# 3_control.net
KiCad netlist of a schematic drawn in Altium Designer
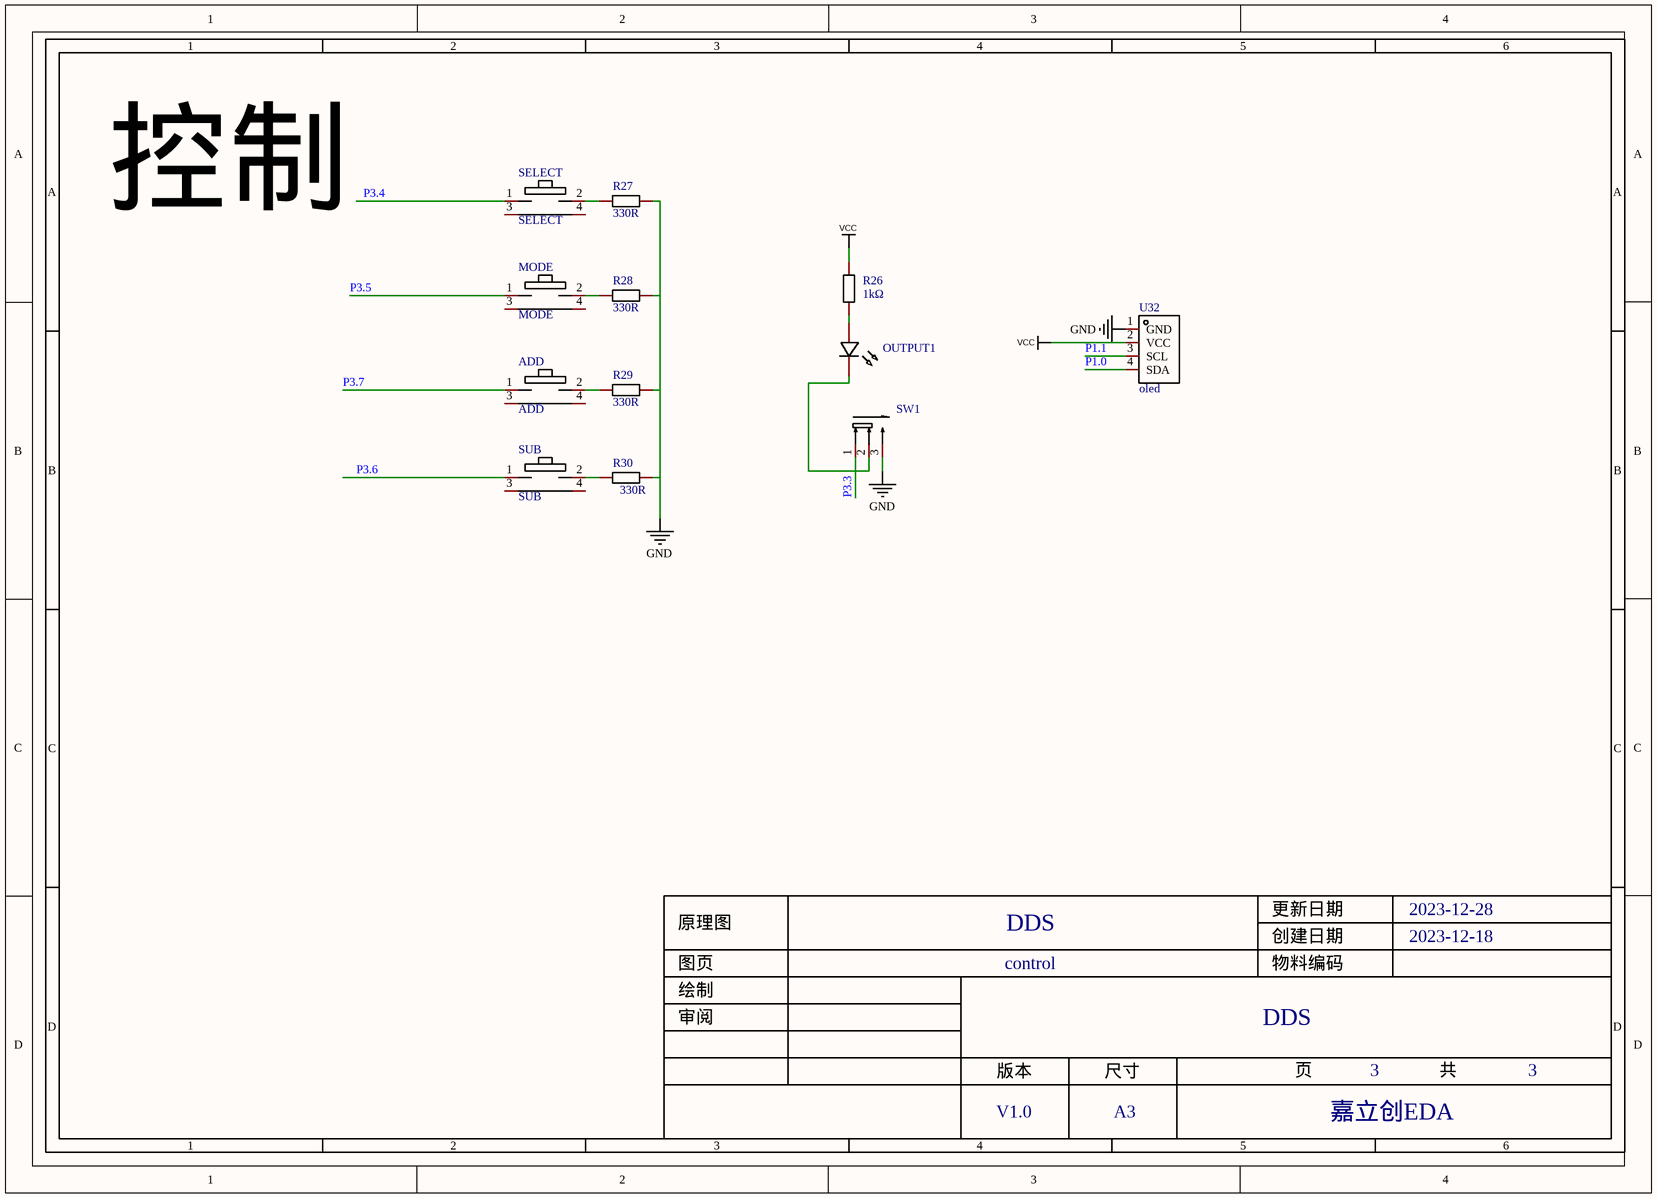
[diagram p0: 3_control.schdoc]

(export (version "E")
  (design (tool "Eeschema 10.0.6"))
  (components
    (comp (ref "ADD")
      (value "ADD")
      (description "电路结构:单刀单掷;按钮作用方向:侧面触动;致动器样式:矩形按钮;照明颜色:-;作用力:180gf ±30gf;开关高度:3.5mm;")
      (fields (field (name "NAME") "ADD") (field (name "MANUFACTURER") "Yuandi(元迪)"))
      (libsource (lib "altium-import") (part "root_0_TS-1087B-B2D2_"))
    )
    (comp (ref "MODE")
      (value "MODE")
      (description "电路结构:单刀单掷;按钮作用方向:侧面触动;致动器样式:矩形按钮;照明颜色:-;作用力:180gf ±30gf;开关高度:3.5mm;")
      (fields (field (name "NAME") "MODE") (field (name "MANUFACTURER") "Yuandi(元迪)"))
      (libsource (lib "altium-import") (part "root_0_TS-1087B-B2D2_"))
    )
    (comp (ref "OUTPUT1") (value "LED_B") (libsource (lib "altium-import") (part "root_3_LED_B_")))
    (comp (ref "R26")
      (value "1kΩ")
      (description "阻值:1kΩ;精度:±1%;功率:125mW;温度系数:±100ppm/℃;电阻类型:厚膜电阻;")
      (fields
        (field (name "NAME") "1kΩ")
        (field (name "MANUFACTURER") "UNI-ROYAL(厚声)")
        (field (name "MANUFACTURER PART") "0805W8F1001T5E")
      )
      (libsource (lib "altium-import") (part "root_1_0805W8F1001T5E_"))
    )
    (comp (ref "R27")
      (value "330R")
      (description "阻值:1kΩ;精度:±1%;功率:125mW;温度系数:±100ppm/℃;电阻类型:厚膜电阻;")
      (fields
        (field (name "MANUFACTURER") "UNI-ROYAL(厚声)")
        (field (name "MANUFACTURER PART") "0805W8F1001T5E")
      )
      (libsource (lib "altium-import") (part "root_2_0805W8F1001T5E_"))
    )
    (comp (ref "R28")
      (value "330R")
      (description "阻值:1kΩ;精度:±1%;功率:125mW;温度系数:±100ppm/℃;电阻类型:厚膜电阻;")
      (fields
        (field (name "MANUFACTURER") "UNI-ROYAL(厚声)")
        (field (name "MANUFACTURER PART") "0805W8F1001T5E")
      )
      (libsource (lib "altium-import") (part "root_2_0805W8F1001T5E_"))
    )
    (comp (ref "R29")
      (value "330R")
      (description "阻值:1kΩ;精度:±1%;功率:125mW;温度系数:±100ppm/℃;电阻类型:厚膜电阻;")
      (fields
        (field (name "MANUFACTURER") "UNI-ROYAL(厚声)")
        (field (name "MANUFACTURER PART") "0805W8F1001T5E")
      )
      (libsource (lib "altium-import") (part "root_2_0805W8F1001T5E_"))
    )
    (comp (ref "R30")
      (value "330R")
      (description "阻值:1kΩ;精度:±1%;功率:125mW;温度系数:±100ppm/℃;电阻类型:厚膜电阻;")
      (fields
        (field (name "MANUFACTURER") "UNI-ROYAL(厚声)")
        (field (name "MANUFACTURER PART") "0805W8F1001T5E")
      )
      (libsource (lib "altium-import") (part "root_2_0805W8F1001T5E_"))
    )
    (comp (ref "SELECT")
      (value "SELECT")
      (description "电路结构:单刀单掷;按钮作用方向:侧面触动;致动器样式:矩形按钮;照明颜色:-;作用力:180gf ±30gf;开关高度:3.5mm;")
      (fields (field (name "NAME") "SELECT") (field (name "MANUFACTURER") "Yuandi(元迪)"))
      (libsource (lib "altium-import") (part "root_0_TS-1087B-B2D2_"))
    )
    (comp (ref "SUB")
      (value "SUB")
      (description "电路结构:单刀单掷;按钮作用方向:侧面触动;致动器样式:矩形按钮;照明颜色:-;作用力:180gf ±30gf;开关高度:3.5mm;")
      (fields (field (name "NAME") "SUB") (field (name "MANUFACTURER") "Yuandi(元迪)"))
      (libsource (lib "altium-import") (part "root_0_TS-1087B-B2D2_"))
    )
    (comp (ref "SW1")
      (value "XKB5858-Z-C")
      (fields (field (name "MANUFACTURER") "XKB Connectivity(中国星坤)"))
      (libsource (lib "altium-import") (part "root_0_XKB5858-Z-C_"))
    )
    (comp (ref "U32")
      (value "oled")
      (fields (field (name "NAME") "oled") (field (name "MANUFACTURER") "HS(汉昇)"))
      (libsource (lib "altium-import") (part "root_0_HS96L03W2C03_"))
    )
  )
  (nets
    (net (code "1") (name "/P1.0") (class "Default")
      (node (ref "U32") (pin "4") (pinfunction "SDA_4") (pintype "passive"))
    )
    (net (code "2") (name "/P1.1") (class "Default")
      (node (ref "U32") (pin "3") (pinfunction "SCL_3") (pintype "passive"))
    )
    (net (code "3") (name "/P3.3") (class "Default")
      (node (ref "OUTPUT1") (pin "1") (pinfunction "C_1") (pintype "passive"))
      (node (ref "SW1") (pin "1") (pinfunction "1_1") (pintype "passive"))
      (node (ref "SW1") (pin "2") (pinfunction "2_2") (pintype "passive"))
    )
    (net (code "4") (name "/P3.4") (class "Default")
      (node (ref "SELECT") (pin "1") (pinfunction "1_1") (pintype "passive"))
    )
    (net (code "5") (name "/P3.5") (class "Default")
      (node (ref "MODE") (pin "1") (pinfunction "1_1") (pintype "passive"))
    )
    (net (code "6") (name "/P3.6") (class "Default")
      (node (ref "SUB") (pin "1") (pinfunction "1_1") (pintype "passive"))
    )
    (net (code "7") (name "/P3.7") (class "Default")
      (node (ref "ADD") (pin "1") (pinfunction "1_1") (pintype "passive"))
    )
    (net (code "8") (name "GND") (class "Default")
      (node (ref "R27") (pin "1") (pinfunction "1_1") (pintype "passive"))
      (node (ref "R28") (pin "1") (pinfunction "1_1") (pintype "passive"))
      (node (ref "R29") (pin "1") (pinfunction "1_1") (pintype "passive"))
      (node (ref "R30") (pin "1") (pinfunction "1_1") (pintype "passive"))
      (node (ref "SW1") (pin "3") (pinfunction "3_3") (pintype "passive"))
      (node (ref "U32") (pin "1") (pinfunction "GND_1") (pintype "passive"))
    )
    (net (code "9") (name "Net-(ADD-Pad2)") (class "Default")
      (node (ref "ADD") (pin "2") (pinfunction "2_2") (pintype "passive"))
      (node (ref "R29") (pin "2") (pinfunction "2_2") (pintype "passive"))
    )
    (net (code "10") (name "Net-(MODE-Pad2)") (class "Default")
      (node (ref "MODE") (pin "2") (pinfunction "2_2") (pintype "passive"))
      (node (ref "R28") (pin "2") (pinfunction "2_2") (pintype "passive"))
    )
    (net (code "11") (name "Net-(OUTPUT1-A)") (class "Default")
      (node (ref "OUTPUT1") (pin "2") (pinfunction "A_2") (pintype "passive"))
      (node (ref "R26") (pin "1") (pinfunction "1_1") (pintype "passive"))
    )
    (net (code "12") (name "Net-(R27-Pad2)") (class "Default")
      (node (ref "R27") (pin "2") (pinfunction "2_2") (pintype "passive"))
      (node (ref "SELECT") (pin "2") (pinfunction "2_2") (pintype "passive"))
    )
    (net (code "13") (name "Net-(R30-Pad2)") (class "Default")
      (node (ref "R30") (pin "2") (pinfunction "2_2") (pintype "passive"))
      (node (ref "SUB") (pin "2") (pinfunction "2_2") (pintype "passive"))
    )
    (net (code "14") (name "VCC") (class "Default")
      (node (ref "R26") (pin "2") (pinfunction "2_2") (pintype "passive"))
      (node (ref "U32") (pin "2") (pinfunction "VCC_2") (pintype "passive"))
    )
    (net (code "15") (name "unconnected-(ADD-Pad3)") (class "Default")
      (node (ref "ADD") (pin "3") (pinfunction "3_3") (pintype "passive"))
    )
    (net (code "16") (name "unconnected-(ADD-Pad4)") (class "Default")
      (node (ref "ADD") (pin "4") (pinfunction "4_4") (pintype "passive"))
    )
    (net (code "17") (name "unconnected-(MODE-Pad3)") (class "Default")
      (node (ref "MODE") (pin "3") (pinfunction "3_3") (pintype "passive"))
    )
    (net (code "18") (name "unconnected-(MODE-Pad4)") (class "Default")
      (node (ref "MODE") (pin "4") (pinfunction "4_4") (pintype "passive"))
    )
    (net (code "19") (name "unconnected-(SELECT-Pad3)") (class "Default")
      (node (ref "SELECT") (pin "3") (pinfunction "3_3") (pintype "passive"))
    )
    (net (code "20") (name "unconnected-(SELECT-Pad4)") (class "Default")
      (node (ref "SELECT") (pin "4") (pinfunction "4_4") (pintype "passive"))
    )
    (net (code "21") (name "unconnected-(SUB-Pad3)") (class "Default")
      (node (ref "SUB") (pin "3") (pinfunction "3_3") (pintype "passive"))
    )
    (net (code "22") (name "unconnected-(SUB-Pad4)") (class "Default")
      (node (ref "SUB") (pin "4") (pinfunction "4_4") (pintype "passive"))
    )
  )
)
